# 3_InfoPerif.net
KiCad netlist of a schematic drawn in Altium Designer
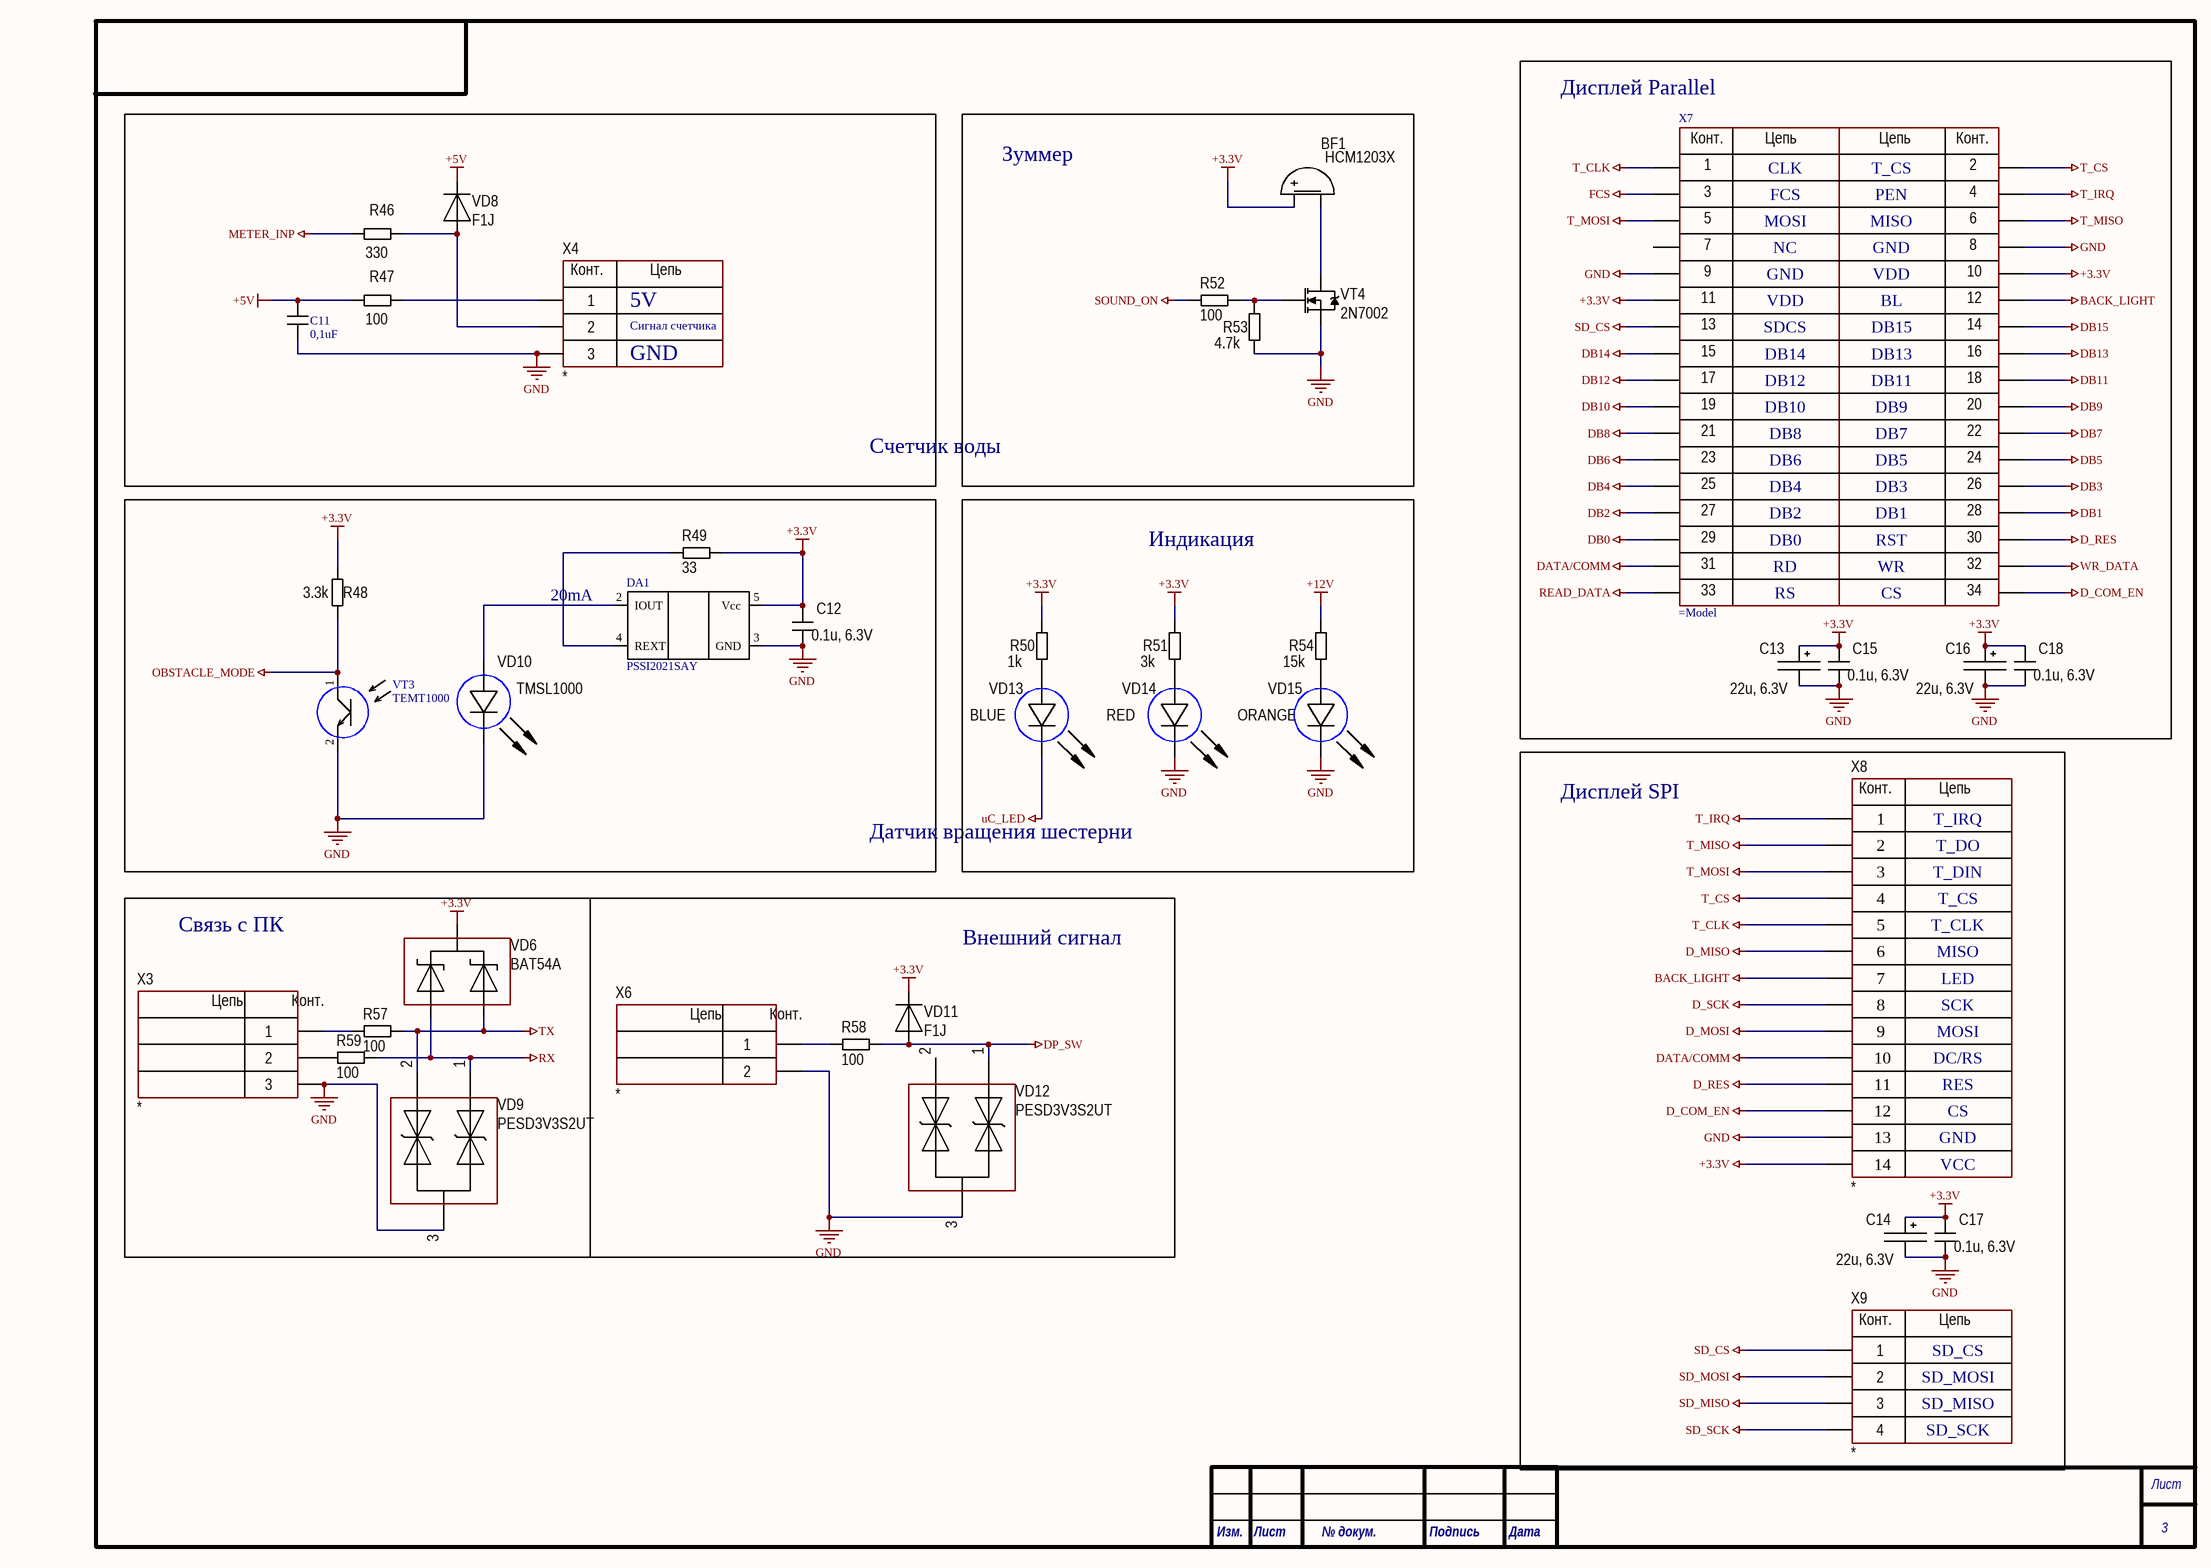
[diagram p0: 3_InfoPerif.SchDoc]

(export (version "E")
  (design (tool "Eeschema 10.0.6"))
  (components
    (comp (ref "BF1")
      (value "HCM1203X")
      (footprint "BUZ: AI-1223-TWT-3V-2-R")
      (fields (field (name "MANUFACTURER") "PUI Audio, Inc."))
      (libsource (lib "Melochi") (part "Buzzer"))
    )
    (comp (ref "C11") (value "0,1uF") (footprint "C_0603") (libsource (lib "Condensators") (part "C_SMD")))
    (comp (ref "C12")
      (value "0.1u, 6.3V")
      (footprint "CH0805C")
      (description "0805")
      (libsource (lib "Condensators") (part "Capacitor"))
    )
    (comp (ref "C13")
      (value "22u, 6.3V")
      (footprint "TANTAL_B")
      (libsource (lib "Condensators") (part "TantalCap"))
    )
    (comp (ref "C14")
      (value "22u, 6.3V")
      (footprint "TANTAL_B")
      (libsource (lib "Condensators") (part "TantalCap"))
    )
    (comp (ref "C15")
      (value "0.1u, 6.3V")
      (footprint "CH0805C")
      (libsource (lib "Condensators") (part "Capacitor"))
    )
    (comp (ref "C16")
      (value "22u, 6.3V")
      (footprint "TANTAL_B")
      (libsource (lib "Condensators") (part "TantalCap"))
    )
    (comp (ref "C17")
      (value "0.1u, 6.3V")
      (footprint "CH0805C")
      (libsource (lib "Condensators") (part "Capacitor"))
    )
    (comp (ref "C18")
      (value "0.1u, 6.3V")
      (footprint "CH0805C")
      (libsource (lib "Condensators") (part "Capacitor"))
    )
    (comp (ref "DA1")
      (value "PSSI2021SAY")
      (footprint "SOT353")
      (description "Iout = 0.617/Rext + 15 µA")
      (libsource (lib "MicroIC") (part "PSSI2021SAY"))
    )
    (comp (ref "R46") (value "330") (footprint "CH0805R") (libsource (lib "Resistors") (part "Resistor")))
    (comp (ref "R47") (value "100") (footprint "CH2512R") (libsource (lib "Resistors") (part "Resistor")))
    (comp (ref "R48")
      (value "3.3k")
      (footprint "CH0805R")
      (description "0805")
      (libsource (lib "Resistors") (part "Resistor"))
    )
    (comp (ref "R49")
      (value "33")
      (footprint "CH0805R")
      (description "0805")
      (libsource (lib "Resistors") (part "Resistor"))
    )
    (comp (ref "R50") (value "1k") (footprint "CH0805R") (libsource (lib "Resistors") (part "Resistor")))
    (comp (ref "R51") (value "3k") (footprint "CH0805R") (libsource (lib "Resistors") (part "Resistor")))
    (comp (ref "R52") (value "100") (footprint "CH0805R") (libsource (lib "Resistors") (part "Resistor")))
    (comp (ref "R53") (value "4.7k") (footprint "CH0805R") (libsource (lib "Resistors") (part "Resistor")))
    (comp (ref "R54") (value "15k") (footprint "CH0805R") (libsource (lib "Resistors") (part "Resistor")))
    (comp (ref "R57") (value "100") (footprint "CH0805R") (libsource (lib "Resistors") (part "Resistor")))
    (comp (ref "R58") (value "100") (footprint "CH0805R") (libsource (lib "Resistors") (part "Resistor")))
    (comp (ref "R59") (value "100") (footprint "CH0805R") (libsource (lib "Resistors") (part "Resistor")))
    (comp (ref "VD6")
      (value "BAT54A")
      (footprint "SOT23_123")
      (libsource (lib "Diods") (part "Diod Schottky Array v.1"))
    )
    (comp (ref "VD8") (value "F1J") (footprint "SOD123F") (libsource (lib "Diods") (part "Diod")))
    (comp (ref "VD9")
      (value "PESD3V3S2UT")
      (footprint "SOT23_132")
      (libsource (lib "Diods") (part "TVS Array"))
    )
    (comp (ref "VD10") (value "TMSL1000") (footprint "TSML1000") (libsource (lib "Diods") (part "LED_1")))
    (comp (ref "VD11") (value "F1J") (footprint "SOD123F") (libsource (lib "Diods") (part "Diod")))
    (comp (ref "VD12")
      (value "PESD3V3S2UT")
      (footprint "SOT23_132")
      (libsource (lib "Diods") (part "TVS Array"))
    )
    (comp (ref "VD13") (value "BLUE") (footprint "CH0603LB") (libsource (lib "Diods") (part "LED_1")))
    (comp (ref "VD14") (value "RED") (footprint "CH0603LB") (libsource (lib "Diods") (part "LED_1")))
    (comp (ref "VD15") (value "ORANGE") (footprint "CH0603LB") (libsource (lib "Diods") (part "LED_1")))
    (comp (ref "VT3")
      (value "TEMT1000")
      (footprint "standard:TEMT1000")
      (libsource (lib "Tranzistor") (part "TEMT1000"))
    )
    (comp (ref "VT4")
      (value "2N7002")
      (footprint "SOT23_123")
      (description "Mosfet")
      (libsource (lib "Tranzistor") (part "N-chanel"))
    )
    (comp (ref "X3") (value "*") (footprint "CON: CWF-3") (libsource (lib "") (part "3-Connector_1")))
    (comp (ref "X4") (value "*") (footprint "CON: CWF-3") (libsource (lib "Connectors") (part "3-Connector")))
    (comp (ref "X6") (value "*") (footprint "CON: CWF-2") (libsource (lib "Connectors") (part "2-Connector")))
    (comp (ref "X7") (value "~") (footprint "DS1023-34") (libsource (lib "Connectors") (part "34-Connector")))
    (comp (ref "X8") (value "*") (footprint "DS1024-14") (libsource (lib "Connectors") (part "14-Connector")))
    (comp (ref "X9") (value "*") (footprint "DS1023-4") (libsource (lib "Connectors") (part "4-Connector")))
  )
  (nets
    (net (code "1") (name "+3.3V") (class "Default")
      (node (ref "BF1") (pin "1") (pinfunction "+_1") (pintype "passive"))
      (node (ref "C12") (pin "2") (pinfunction "2_2") (pintype "passive"))
      (node (ref "C13") (pin "1") (pinfunction "1_1") (pintype "power_in"))
      (node (ref "C14") (pin "1") (pinfunction "1_1") (pintype "power_in"))
      (node (ref "C15") (pin "2") (pinfunction "2_2") (pintype "passive"))
      (node (ref "C16") (pin "1") (pinfunction "1_1") (pintype "power_in"))
      (node (ref "C17") (pin "2") (pinfunction "2_2") (pintype "passive"))
      (node (ref "C18") (pin "2") (pinfunction "2_2") (pintype "passive"))
      (node (ref "DA1") (pin "5") (pinfunction "Vcc_5") (pintype "passive"))
      (node (ref "R48") (pin "2") (pinfunction "2_2") (pintype "passive"))
      (node (ref "R49") (pin "2") (pinfunction "2_2") (pintype "passive"))
      (node (ref "R50") (pin "2") (pinfunction "2_2") (pintype "passive"))
      (node (ref "R51") (pin "2") (pinfunction "2_2") (pintype "passive"))
      (node (ref "VD11") (pin "2") (pinfunction "2_2") (pintype "passive"))
      (node (ref "VD6") (pin "2") (pinfunction "2_2") (pintype "passive"))
      (node (ref "X7") (pin "10") (pintype "passive"))
      (node (ref "X7") (pin "11") (pintype "passive"))
      (node (ref "X8") (pin "14") (pinfunction "14_14") (pintype "power_in"))
    )
    (net (code "2") (name "+5V") (class "Default")
      (node (ref "C11") (pin "2") (pinfunction "2_2") (pintype "passive"))
      (node (ref "R47") (pin "1") (pinfunction "1_1") (pintype "passive"))
      (node (ref "VD8") (pin "2") (pinfunction "2_2") (pintype "passive"))
    )
    (net (code "3") (name "+12V") (class "Default")
      (node (ref "R54") (pin "2") (pinfunction "2_2") (pintype "passive"))
    )
    (net (code "4") (name "BACK_LIGHT") (class "Default")
      (node (ref "X7") (pin "12") (pintype "passive"))
      (node (ref "X8") (pin "7") (pinfunction "7_7") (pintype "power_in"))
    )
    (net (code "5") (name "DATA{slash}COMM") (class "Default")
      (node (ref "X7") (pin "31") (pintype "passive"))
      (node (ref "X8") (pin "10") (pinfunction "10_10") (pintype "power_in"))
    )
    (net (code "6") (name "DB0") (class "Default") (node (ref "X7") (pin "29") (pintype "passive")))
    (net (code "7") (name "DB1") (class "Default") (node (ref "X7") (pin "28") (pintype "passive")))
    (net (code "8") (name "DB2") (class "Default") (node (ref "X7") (pin "27") (pintype "passive")))
    (net (code "9") (name "DB3") (class "Default") (node (ref "X7") (pin "26") (pintype "passive")))
    (net (code "10") (name "DB4") (class "Default") (node (ref "X7") (pin "25") (pintype "passive")))
    (net (code "11") (name "DB5") (class "Default") (node (ref "X7") (pin "24") (pintype "passive")))
    (net (code "12") (name "DB6") (class "Default") (node (ref "X7") (pin "23") (pintype "passive")))
    (net (code "13") (name "DB7") (class "Default") (node (ref "X7") (pin "22") (pintype "passive")))
    (net (code "14") (name "DB8") (class "Default") (node (ref "X7") (pin "21") (pintype "passive")))
    (net (code "15") (name "DB9") (class "Default") (node (ref "X7") (pin "20") (pintype "passive")))
    (net (code "16") (name "DB10") (class "Default") (node (ref "X7") (pin "19") (pintype "passive")))
    (net (code "17") (name "DB11") (class "Default") (node (ref "X7") (pin "18") (pintype "passive")))
    (net (code "18") (name "DB12") (class "Default") (node (ref "X7") (pin "17") (pintype "passive")))
    (net (code "19") (name "DB13") (class "Default") (node (ref "X7") (pin "16") (pintype "passive")))
    (net (code "20") (name "DB14") (class "Default") (node (ref "X7") (pin "15") (pintype "passive")))
    (net (code "21") (name "DB15") (class "Default") (node (ref "X7") (pin "14") (pintype "passive")))
    (net (code "22") (name "DP_SW") (class "Default")
      (node (ref "R58") (pin "2") (pinfunction "2_2") (pintype "passive"))
      (node (ref "VD11") (pin "1") (pinfunction "1_1") (pintype "passive"))
      (node (ref "VD12") (pin "1") (pintype "passive"))
    )
    (net (code "23") (name "D_COM_EN") (class "Default")
      (node (ref "X7") (pin "34") (pintype "passive"))
      (node (ref "X8") (pin "12") (pinfunction "12_12") (pintype "power_in"))
    )
    (net (code "24") (name "D_MISO") (class "Default")
      (node (ref "X8") (pin "6") (pinfunction "6_6") (pintype "power_in"))
    )
    (net (code "25") (name "D_MOSI") (class "Default")
      (node (ref "X8") (pin "9") (pinfunction "9_9") (pintype "power_in"))
    )
    (net (code "26") (name "D_RES") (class "Default")
      (node (ref "X7") (pin "30") (pintype "passive"))
      (node (ref "X8") (pin "11") (pinfunction "11_11") (pintype "power_in"))
    )
    (net (code "27") (name "D_SCK") (class "Default")
      (node (ref "X8") (pin "8") (pinfunction "8_8") (pintype "power_in"))
    )
    (net (code "28") (name "FCS") (class "Default") (node (ref "X7") (pin "3") (pintype "passive")))
    (net (code "29") (name "GND") (class "Default")
      (node (ref "C11") (pin "1") (pinfunction "1_1") (pintype "passive"))
      (node (ref "C12") (pin "1") (pinfunction "1_1") (pintype "passive"))
      (node (ref "C13") (pin "2") (pinfunction "2_2") (pintype "power_in"))
      (node (ref "C14") (pin "2") (pinfunction "2_2") (pintype "power_in"))
      (node (ref "C15") (pin "1") (pinfunction "1_1") (pintype "passive"))
      (node (ref "C16") (pin "2") (pinfunction "2_2") (pintype "power_in"))
      (node (ref "C17") (pin "1") (pinfunction "1_1") (pintype "passive"))
      (node (ref "C18") (pin "1") (pinfunction "1_1") (pintype "passive"))
      (node (ref "DA1") (pin "3") (pinfunction "GND_3") (pintype "passive"))
      (node (ref "R53") (pin "1") (pinfunction "1_1") (pintype "passive"))
      (node (ref "VD10") (pin "2") (pinfunction "C_2") (pintype "passive"))
      (node (ref "VD12") (pin "3") (pintype "passive"))
      (node (ref "VD14") (pin "2") (pinfunction "C_2") (pintype "passive"))
      (node (ref "VD15") (pin "2") (pinfunction "C_2") (pintype "passive"))
      (node (ref "VD9") (pin "3") (pintype "passive"))
      (node (ref "VT3") (pin "2") (pinfunction "2_2") (pintype "passive"))
      (node (ref "VT4") (pin "3") (pinfunction "S_3") (pintype "passive"))
      (node (ref "X3") (pin "3") (pinfunction "3_3") (pintype "passive"))
      (node (ref "X4") (pin "3") (pinfunction "3_3") (pintype "passive"))
      (node (ref "X6") (pin "2") (pinfunction "2_2") (pintype "passive"))
      (node (ref "X7") (pin "8") (pintype "passive"))
      (node (ref "X7") (pin "9") (pintype "passive"))
      (node (ref "X8") (pin "13") (pinfunction "13_13") (pintype "power_in"))
    )
    (net (code "30") (name "METER_INP") (class "Default")
      (node (ref "R46") (pin "1") (pinfunction "1_1") (pintype "passive"))
    )
    (net (code "31") (name "Net-(BF1--)") (class "Default")
      (node (ref "BF1") (pin "2") (pinfunction "-_2") (pintype "passive"))
      (node (ref "VT4") (pin "2") (pinfunction "D_2") (pintype "passive"))
    )
    (net (code "32") (name "Net-(DA1-IOUT)") (class "Default")
      (node (ref "DA1") (pin "2") (pinfunction "IOUT_2") (pintype "passive"))
      (node (ref "VD10") (pin "1") (pinfunction "A_1") (pintype "passive"))
    )
    (net (code "33") (name "Net-(DA1-REXT)") (class "Default")
      (node (ref "DA1") (pin "4") (pinfunction "REXT_4") (pintype "passive"))
      (node (ref "R49") (pin "1") (pinfunction "1_1") (pintype "passive"))
    )
    (net (code "34") (name "Net-(R46-Pad2)") (class "Default")
      (node (ref "R46") (pin "2") (pinfunction "2_2") (pintype "passive"))
      (node (ref "VD8") (pin "1") (pinfunction "1_1") (pintype "passive"))
      (node (ref "X4") (pin "2") (pinfunction "2_2") (pintype "passive"))
    )
    (net (code "35") (name "Net-(R47-Pad2)") (class "Default")
      (node (ref "R47") (pin "2") (pinfunction "2_2") (pintype "passive"))
      (node (ref "X4") (pin "1") (pinfunction "1_1") (pintype "passive"))
    )
    (net (code "36") (name "Net-(R57-Pad1)") (class "Default")
      (node (ref "R57") (pin "1") (pinfunction "1_1") (pintype "passive"))
      (node (ref "X3") (pin "1") (pinfunction "1_1") (pintype "passive"))
    )
    (net (code "37") (name "Net-(R58-Pad1)") (class "Default")
      (node (ref "R58") (pin "1") (pinfunction "1_1") (pintype "passive"))
      (node (ref "X6") (pin "1") (pinfunction "1_1") (pintype "passive"))
    )
    (net (code "38") (name "Net-(R59-Pad1)") (class "Default")
      (node (ref "R59") (pin "1") (pinfunction "1_1") (pintype "passive"))
      (node (ref "X3") (pin "2") (pinfunction "2_2") (pintype "passive"))
    )
    (net (code "39") (name "Net-(VD13-A)") (class "Default")
      (node (ref "R50") (pin "1") (pinfunction "1_1") (pintype "passive"))
      (node (ref "VD13") (pin "1") (pinfunction "A_1") (pintype "passive"))
    )
    (net (code "40") (name "Net-(VD14-A)") (class "Default")
      (node (ref "R51") (pin "1") (pinfunction "1_1") (pintype "passive"))
      (node (ref "VD14") (pin "1") (pinfunction "A_1") (pintype "passive"))
    )
    (net (code "41") (name "Net-(VD15-A)") (class "Default")
      (node (ref "R54") (pin "1") (pinfunction "1_1") (pintype "passive"))
      (node (ref "VD15") (pin "1") (pinfunction "A_1") (pintype "passive"))
    )
    (net (code "42") (name "Net-(VT4-G)") (class "Default")
      (node (ref "R52") (pin "1") (pinfunction "1_1") (pintype "passive"))
      (node (ref "R53") (pin "2") (pinfunction "2_2") (pintype "passive"))
      (node (ref "VT4") (pin "1") (pinfunction "G_1") (pintype "passive"))
    )
    (net (code "43") (name "OBSTACLE_MODE") (class "Default")
      (node (ref "R48") (pin "1") (pinfunction "1_1") (pintype "passive"))
      (node (ref "VT3") (pin "1") (pinfunction "1_1") (pintype "passive"))
    )
    (net (code "44") (name "READ_DATA") (class "Default") (node (ref "X7") (pin "33") (pintype "passive")))
    (net (code "45") (name "RX") (class "Default")
      (node (ref "R59") (pin "2") (pinfunction "2_2") (pintype "passive"))
      (node (ref "VD6") (pin "3") (pinfunction "3_3") (pintype "passive"))
      (node (ref "VD9") (pin "1") (pintype "passive"))
    )
    (net (code "46") (name "SD_CS") (class "Default")
      (node (ref "X7") (pin "13") (pintype "passive"))
      (node (ref "X9") (pin "1") (pinfunction "1_1") (pintype "passive"))
    )
    (net (code "47") (name "SD_MISO") (class "Default")
      (node (ref "X9") (pin "3") (pinfunction "3_3") (pintype "power_in"))
    )
    (net (code "48") (name "SD_MOSI") (class "Default")
      (node (ref "X9") (pin "2") (pinfunction "2_2") (pintype "passive"))
    )
    (net (code "49") (name "SD_SCK") (class "Default")
      (node (ref "X9") (pin "4") (pinfunction "4_4") (pintype "power_in"))
    )
    (net (code "50") (name "SOUND_ON") (class "Default")
      (node (ref "R52") (pin "2") (pinfunction "2_2") (pintype "passive"))
    )
    (net (code "51") (name "TX") (class "Default")
      (node (ref "R57") (pin "2") (pinfunction "2_2") (pintype "passive"))
      (node (ref "VD6") (pin "1") (pinfunction "1_1") (pintype "passive"))
      (node (ref "VD9") (pin "2") (pintype "passive"))
    )
    (net (code "52") (name "T_CLK") (class "Default")
      (node (ref "X7") (pin "1") (pintype "passive"))
      (node (ref "X8") (pin "5") (pinfunction "5_5") (pintype "power_in"))
    )
    (net (code "53") (name "T_CS") (class "Default")
      (node (ref "X7") (pin "2") (pintype "passive"))
      (node (ref "X8") (pin "4") (pinfunction "4_4") (pintype "power_in"))
    )
    (net (code "54") (name "T_IRQ") (class "Default")
      (node (ref "X7") (pin "4") (pintype "passive"))
      (node (ref "X8") (pin "1") (pinfunction "1_1") (pintype "passive"))
    )
    (net (code "55") (name "T_MISO") (class "Default")
      (node (ref "X7") (pin "6") (pintype "passive"))
      (node (ref "X8") (pin "2") (pinfunction "2_2") (pintype "passive"))
    )
    (net (code "56") (name "T_MOSI") (class "Default")
      (node (ref "X7") (pin "5") (pintype "passive"))
      (node (ref "X8") (pin "3") (pinfunction "3_3") (pintype "power_in"))
    )
    (net (code "57") (name "WR_DATA") (class "Default") (node (ref "X7") (pin "32") (pintype "passive")))
    (net (code "58") (name "uC_LED") (class "Default")
      (node (ref "VD13") (pin "2") (pinfunction "C_2") (pintype "passive"))
    )
    (net (code "59") (name "unconnected-(VD12-Pad2)") (class "Default")
      (node (ref "VD12") (pin "2") (pintype "passive"))
    )
    (net (code "60") (name "unconnected-(X7-Pad7)") (class "Default")
      (node (ref "X7") (pin "7") (pintype "passive"))
    )
  )
)
